# MCU.net
KiCad netlist of a schematic drawn in Altium Designer
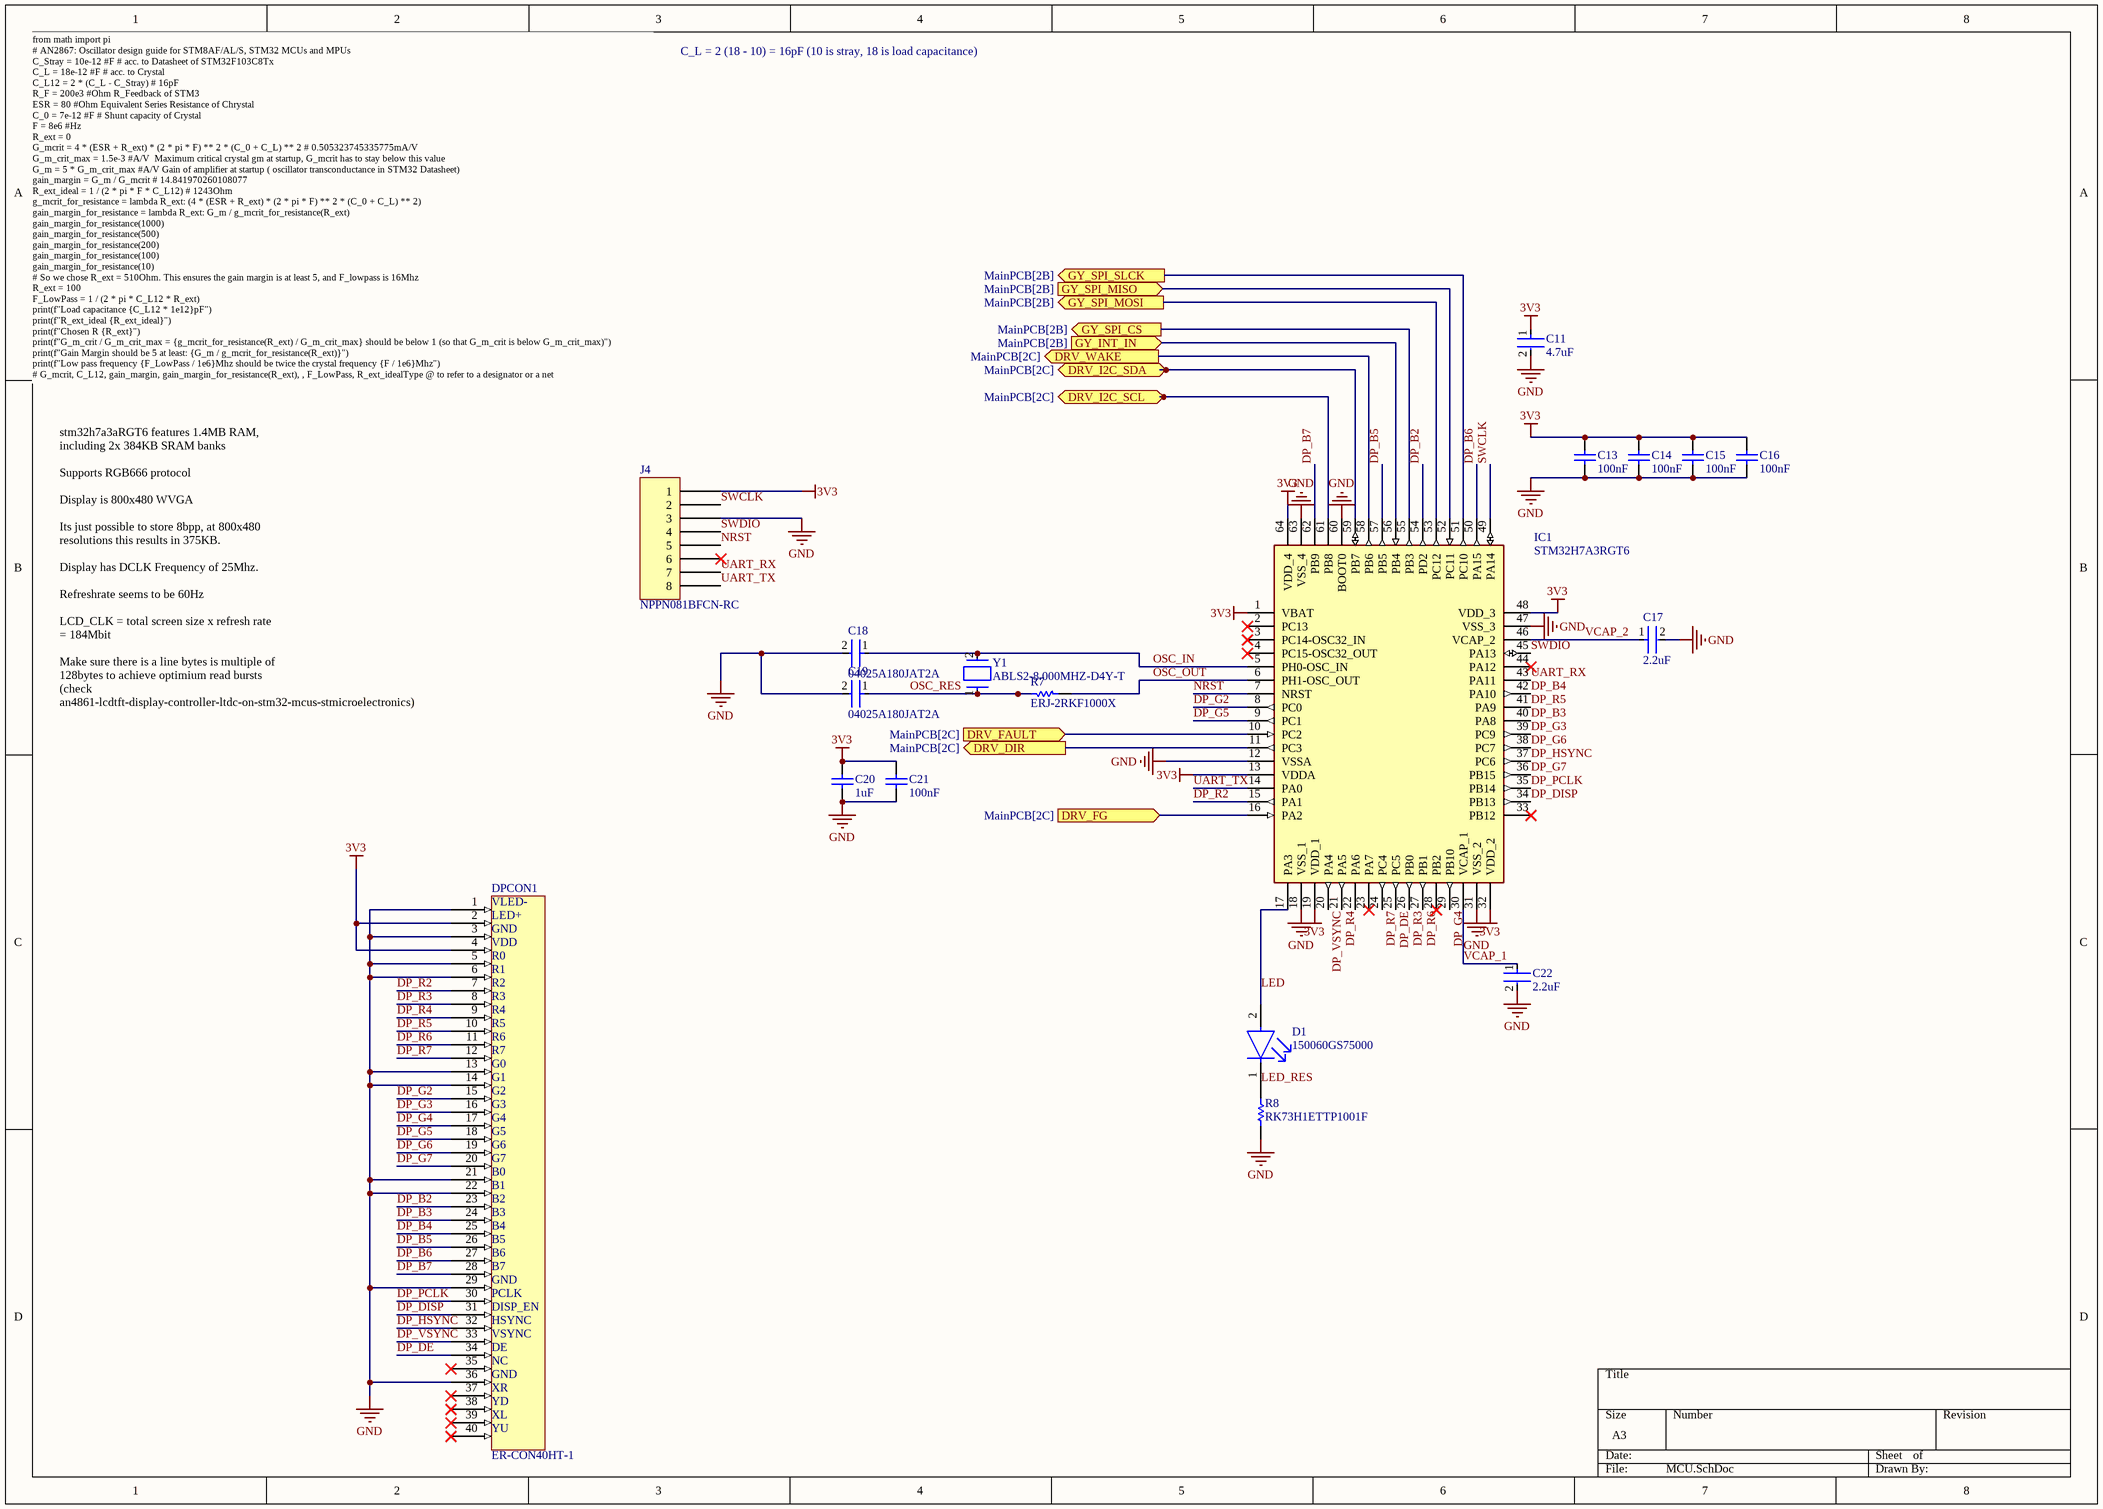
[diagram p0: MCU.SchDoc]

(export (version "E")
  (design (tool "Eeschema 10.0.6"))
  (components
    (comp (ref "C11")
      (value "4.7uF")
      (footprint "FP-C1005-050-0_15-MFG")
      (description "CAP CER 4.7UF 10V X5R 0402 C1005X5R1A475K050BC")
      (fields (field (name "TOLERANCE") "10%"))
      (libsource (lib "Altium Content Vault") (part "b4654b650e69147ec39a6b967a45e02"))
    )
    (comp (ref "C13")
      (value "100nF")
      (footprint "CAPC1005X56X25LL10T15")
      (description "04026D104KAT2A")
      (fields (field (name "MANUFACTURER") "AVX Interconnect / Elco"))
      (libsource (lib "Altium Content Vault") (part "CAP"))
    )
    (comp (ref "C14")
      (value "100nF")
      (footprint "CAPC1005X56X25LL10T15")
      (description "04026D104KAT2A")
      (fields (field (name "MANUFACTURER") "AVX Interconnect / Elco"))
      (libsource (lib "Altium Content Vault") (part "CAP"))
    )
    (comp (ref "C15")
      (value "100nF")
      (footprint "CAPC1005X56X25LL10T15")
      (description "04026D104KAT2A")
      (fields (field (name "MANUFACTURER") "AVX Interconnect / Elco"))
      (libsource (lib "Altium Content Vault") (part "CAP"))
    )
    (comp (ref "C16")
      (value "100nF")
      (footprint "CAPC1005X56X25LL10T15")
      (description "04026D104KAT2A")
      (fields (field (name "MANUFACTURER") "AVX Interconnect / Elco"))
      (libsource (lib "Altium Content Vault") (part "CAP"))
    )
    (comp (ref "C17")
      (value "2.2uF")
      (footprint "FP-C1005-050-0_05-IPC_A")
      (description "Multilayer Ceramic Capacitors 2.2μF ±10% 10V X5R SMD 0402 C1005X5R1A225K050BC")
      (fields (field (name "TOLERANCE") "10%") (field (name "VOLTAGE") "10V"))
      (libsource (lib "Altium Content Vault") (part "b4654b650e69147ec39a6b967a45e02"))
    )
    (comp (ref "C18")
      (value "04025A180JAT2A")
      (footprint "FP-0402-L_1_0_1-W_0_5_0_1-MFG")
      (description "General Purpose Ceramic Capacitor, 0402, 18pF, 5%, C0G, 30ppm/°C, 50V")
      (fields (field (name "VOLTAGE") "50V") (field (name "TOLERANCE") "5%"))
      (libsource (lib "Altium Content Vault") (part "b4654b650e69147ec39a6b967a45e02"))
    )
    (comp (ref "C19")
      (value "04025A180JAT2A")
      (footprint "FP-0402-L_1_0_1-W_0_5_0_1-MFG")
      (description "General Purpose Ceramic Capacitor, 0402, 18pF, 5%, C0G, 30ppm/°C, 50V")
      (fields (field (name "VOLTAGE") "50V") (field (name "TOLERANCE") "5%"))
      (libsource (lib "Altium Content Vault") (part "b4654b650e69147ec39a6b967a45e02"))
    )
    (comp (ref "C20")
      (value "1uF")
      (footprint "CAPC1005X60X30NL05T10")
      (description "C0402C105M8PACTU")
      (fields (field (name "MANUFACTURER") "Kemet"))
      (libsource (lib "Altium Content Vault") (part "CAP"))
    )
    (comp (ref "C21")
      (value "100nF")
      (footprint "CAPC1005X56X25LL10T15")
      (description "04026D104KAT2A")
      (fields (field (name "MANUFACTURER") "AVX Interconnect / Elco"))
      (libsource (lib "Altium Content Vault") (part "CAP"))
    )
    (comp (ref "C22")
      (value "2.2uF")
      (footprint "FP-C1005-050-0_05-IPC_A")
      (description "Multilayer Ceramic Capacitors 2.2μF ±10% 10V X5R SMD 0402 C1005X5R1A225K050BC")
      (fields (field (name "TOLERANCE") "10%") (field (name "VOLTAGE") "10V"))
      (libsource (lib "Altium Content Vault") (part "b4654b650e69147ec39a6b967a45e02"))
    )
    (comp (ref "D1")
      (value "150060GS75000")
      (footprint "FP-150060GS75000-MFG")
      (description "LED GREEN CLEAR 0603 SMD")
      (libsource (lib "Altium Content Vault") (part "8706943c75ba83719d021d2fdc84c58"))
    )
    (comp (ref "DPCON1")
      (value "ER-CON40HT-1")
      (footprint "ER-CON40HT-1")
      (fields (field (name "MANUFACTURER") "EastRising"))
      (libsource (lib "Schlib1") (part "ER-CON40HT-1"))
    )
    (comp (ref "IC1")
      (value "STM32H7A3RGT6")
      (footprint "SamacSys:QFP50P1200X1200X160-64N")
      (description "Integrated Circuit")
      (fields (field (name "MOUSER PART NUMBER") "511-STM32H7A3RGT6"))
      (libsource (lib "*") (part "STM32H7A3RGT6"))
    )
    (comp (ref "J4")
      (value "NPPN081BFCN-RC")
      (footprint "SULLINS NPPN081BFCN")
      (description "CONN HDR 8POS 0.079 GOLD PCB")
      (fields (field (name "MANUFACTURER") "Sullins Connector Solutions"))
      (libsource (lib "Celestial Altium Library") (part "8 Pin"))
    )
    (comp (ref "R7")
      (value "ERJ-2RKF1000X")
      (footprint "RESC1005X40X25LL05T05")
      (description "Chip Resistor, 100 Ohm, +/- 1%, 100 mW, -55 to 155 degC, 0402 (1005 Metric), RoHS, Tape and Reel")
      (fields (field (name "MANUFACTURER") "Basic Passives") (field (name "TOLERANCE") "1%"))
      (libsource (lib "Altium Content Vault") (part "RES-2"))
    )
    (comp (ref "R8")
      (value "RK73H1ETTP1001F")
      (footprint "RESC1005X40X25LL10T10")
      (fields (field (name "MANUFACTURER") "KOA Speer"))
      (libsource (lib "Altium Content Vault") (part "RES"))
    )
    (comp (ref "Y1")
      (value "ABLS2-8.000MHZ-D4Y-T")
      (footprint "FP-ABLS2-MFG")
      (description "CRYSTAL 8.0000MHZ 18PF SMD")
      (fields (field (name "TOLERANCE") "30ppm"))
      (libsource (lib "Altium Content Vault") (part "c23a69dc6c9e2f18f2079038eb95dd1"))
    )
  )
  (nets
    (net (code "1") (name "/DP_B2") (class "Default")
      (node (ref "DPCON1") (pin "23") (pintype "input"))
      (node (ref "IC1") (pin "54") (pinfunction "PD2_54") (pintype "output"))
    )
    (net (code "2") (name "/DP_B3") (class "Default")
      (node (ref "DPCON1") (pin "24") (pintype "input"))
      (node (ref "IC1") (pin "40") (pinfunction "PA8_40") (pintype "open_collector"))
    )
    (net (code "3") (name "/DP_B4") (class "Default")
      (node (ref "DPCON1") (pin "25") (pintype "input"))
      (node (ref "IC1") (pin "42") (pinfunction "PA10_42") (pintype "output"))
    )
    (net (code "4") (name "/DP_B5") (class "Default")
      (node (ref "DPCON1") (pin "26") (pintype "input"))
      (node (ref "IC1") (pin "57") (pinfunction "PB5_57") (pintype "output"))
    )
    (net (code "5") (name "/DP_B6") (class "Default")
      (node (ref "DPCON1") (pin "27") (pintype "input"))
      (node (ref "IC1") (pin "50") (pinfunction "PA15_50") (pintype "output"))
    )
    (net (code "6") (name "/DP_B7") (class "Default")
      (node (ref "DPCON1") (pin "28") (pintype "input"))
      (node (ref "IC1") (pin "62") (pinfunction "PB9_62") (pintype "open_collector"))
    )
    (net (code "7") (name "/DP_DE") (class "Default")
      (node (ref "DPCON1") (pin "34") (pintype "input"))
      (node (ref "IC1") (pin "25") (pinfunction "PC5_25") (pintype "output"))
    )
    (net (code "8") (name "/DP_DISP") (class "Default")
      (node (ref "DPCON1") (pin "31") (pintype "input"))
      (node (ref "IC1") (pin "34") (pinfunction "PB13_34") (pintype "output"))
    )
    (net (code "9") (name "/DP_G2") (class "Default")
      (node (ref "DPCON1") (pin "15") (pintype "input"))
      (node (ref "IC1") (pin "8") (pinfunction "PC0_8") (pintype "output"))
    )
    (net (code "10") (name "/DP_G3") (class "Default")
      (node (ref "DPCON1") (pin "16") (pintype "input"))
      (node (ref "IC1") (pin "39") (pinfunction "PC9_39") (pintype "output"))
    )
    (net (code "11") (name "/DP_G4") (class "Default")
      (node (ref "DPCON1") (pin "17") (pintype "input"))
      (node (ref "IC1") (pin "29") (pinfunction "PB10_29") (pintype "output"))
    )
    (net (code "12") (name "/DP_G5") (class "Default")
      (node (ref "DPCON1") (pin "18") (pintype "input"))
      (node (ref "IC1") (pin "9") (pinfunction "PC1_9") (pintype "output"))
    )
    (net (code "13") (name "/DP_G6") (class "Default")
      (node (ref "DPCON1") (pin "19") (pintype "input"))
      (node (ref "IC1") (pin "38") (pinfunction "PC7_38") (pintype "output"))
    )
    (net (code "14") (name "/DP_G7") (class "Default")
      (node (ref "DPCON1") (pin "20") (pintype "input"))
      (node (ref "IC1") (pin "36") (pinfunction "PB15_36") (pintype "output"))
    )
    (net (code "15") (name "/DP_HSYNC") (class "Default")
      (node (ref "DPCON1") (pin "32") (pintype "input"))
      (node (ref "IC1") (pin "37") (pinfunction "PC6_37") (pintype "output"))
    )
    (net (code "16") (name "/DP_PCLK") (class "Default")
      (node (ref "DPCON1") (pin "30") (pintype "input"))
      (node (ref "IC1") (pin "35") (pinfunction "PB14_35") (pintype "output"))
    )
    (net (code "17") (name "/DP_R2") (class "Default")
      (node (ref "DPCON1") (pin "7") (pintype "input"))
      (node (ref "IC1") (pin "15") (pinfunction "PA1_15") (pintype "output"))
    )
    (net (code "18") (name "/DP_R3") (class "Default")
      (node (ref "DPCON1") (pin "8") (pintype "input"))
      (node (ref "IC1") (pin "26") (pinfunction "PB0_26") (pintype "output"))
    )
    (net (code "19") (name "/DP_R4") (class "Default")
      (node (ref "DPCON1") (pin "9") (pintype "input"))
      (node (ref "IC1") (pin "21") (pinfunction "PA5_21") (pintype "output"))
    )
    (net (code "20") (name "/DP_R5") (class "Default")
      (node (ref "DPCON1") (pin "10") (pintype "input"))
      (node (ref "IC1") (pin "41") (pinfunction "PA9_41") (pintype "open_collector"))
    )
    (net (code "21") (name "/DP_R6") (class "Default")
      (node (ref "DPCON1") (pin "11") (pintype "input"))
      (node (ref "IC1") (pin "27") (pinfunction "PB1_27") (pintype "output"))
    )
    (net (code "22") (name "/DP_R7") (class "Default")
      (node (ref "DPCON1") (pin "12") (pintype "input"))
      (node (ref "IC1") (pin "24") (pinfunction "PC4_24") (pintype "output"))
    )
    (net (code "23") (name "/DP_VSYNC") (class "Default")
      (node (ref "DPCON1") (pin "33") (pintype "input"))
      (node (ref "IC1") (pin "20") (pinfunction "PA4_20") (pintype "output"))
    )
    (net (code "24") (name "/DRV_DIR") (class "Default")
      (node (ref "IC1") (pin "11") (pinfunction "PC3_11") (pintype "output"))
    )
    (net (code "25") (name "/DRV_FAULT") (class "Default")
      (node (ref "IC1") (pin "10") (pinfunction "PC2_10") (pintype "input"))
    )
    (net (code "26") (name "/DRV_FG") (class "Default")
      (node (ref "IC1") (pin "16") (pinfunction "PA2_16") (pintype "input"))
    )
    (net (code "27") (name "/DRV_I2C_SCL") (class "Default")
      (node (ref "IC1") (pin "61") (pinfunction "PB8_61") (pintype "open_collector"))
    )
    (net (code "28") (name "/DRV_I2C_SDA") (class "Default")
      (node (ref "IC1") (pin "59") (pinfunction "PB7_59") (pintype "bidirectional"))
    )
    (net (code "29") (name "/DRV_WAKE") (class "Default")
      (node (ref "IC1") (pin "58") (pinfunction "PB6_58") (pintype "output"))
    )
    (net (code "30") (name "/GY_INT_IN") (class "Default")
      (node (ref "IC1") (pin "56") (pinfunction "PB4_56") (pintype "input"))
    )
    (net (code "31") (name "/GY_SPI_CS") (class "Default")
      (node (ref "IC1") (pin "55") (pinfunction "PB3_55") (pintype "output"))
    )
    (net (code "32") (name "/GY_SPI_MISO") (class "Default")
      (node (ref "IC1") (pin "52") (pinfunction "PC11_52") (pintype "input"))
    )
    (net (code "33") (name "/GY_SPI_MOSI") (class "Default")
      (node (ref "IC1") (pin "53") (pinfunction "PC12_53") (pintype "output"))
    )
    (net (code "34") (name "/GY_SPI_SLCK") (class "Default")
      (node (ref "IC1") (pin "51") (pinfunction "PC10_51") (pintype "output"))
    )
    (net (code "35") (name "/LED") (class "Default")
      (node (ref "D1") (pin "2") (pinfunction "A_2") (pintype "passive"))
      (node (ref "IC1") (pin "17") (pinfunction "PA3_17") (pintype "passive"))
    )
    (net (code "36") (name "/LED_RES") (class "Default")
      (node (ref "D1") (pin "1") (pinfunction "C_1") (pintype "passive"))
      (node (ref "R8") (pin "2") (pinfunction "2_2") (pintype "passive"))
    )
    (net (code "37") (name "/NRST") (class "Default")
      (node (ref "IC1") (pin "7") (pinfunction "NRST_7") (pintype "passive"))
      (node (ref "J4") (pin "5") (pinfunction "5_5") (pintype "passive"))
    )
    (net (code "38") (name "/OSC_IN") (class "Default")
      (node (ref "C18") (pin "1") (pinfunction "1_1") (pintype "passive"))
      (node (ref "IC1") (pin "5") (pinfunction "PH0-OSC_IN_5") (pintype "passive"))
      (node (ref "Y1") (pin "2") (pinfunction "2_2") (pintype "passive"))
    )
    (net (code "39") (name "/OSC_OUT") (class "Default")
      (node (ref "IC1") (pin "6") (pinfunction "PH1-OSC_OUT_6") (pintype "passive"))
      (node (ref "R7") (pin "1") (pinfunction "1_1") (pintype "passive"))
    )
    (net (code "40") (name "/OSC_RES") (class "Default")
      (node (ref "C19") (pin "1") (pinfunction "1_1") (pintype "passive"))
      (node (ref "R7") (pin "2") (pinfunction "2_2") (pintype "passive"))
      (node (ref "Y1") (pin "1") (pinfunction "1_1") (pintype "passive"))
    )
    (net (code "41") (name "/SWCLK") (class "Default")
      (node (ref "IC1") (pin "49") (pinfunction "PA14_49") (pintype "bidirectional"))
      (node (ref "J4") (pin "2") (pinfunction "2_2") (pintype "passive"))
    )
    (net (code "42") (name "/SWDIO") (class "Default")
      (node (ref "IC1") (pin "45") (pinfunction "PA13_45") (pintype "bidirectional"))
      (node (ref "J4") (pin "4") (pinfunction "4_4") (pintype "passive"))
    )
    (net (code "43") (name "/UART_RX") (class "Default")
      (node (ref "IC1") (pin "43") (pinfunction "PA11_43") (pintype "passive"))
      (node (ref "J4") (pin "7") (pinfunction "7_7") (pintype "passive"))
    )
    (net (code "44") (name "/UART_TX") (class "Default")
      (node (ref "IC1") (pin "14") (pinfunction "PA0_14") (pintype "passive"))
      (node (ref "J4") (pin "8") (pinfunction "8_8") (pintype "passive"))
    )
    (net (code "45") (name "/VCAP_1") (class "Default")
      (node (ref "C22") (pin "1") (pinfunction "1_1") (pintype "passive"))
      (node (ref "IC1") (pin "30") (pinfunction "VCAP_1_30") (pintype "passive"))
    )
    (net (code "46") (name "/VCAP_2") (class "Default")
      (node (ref "C17") (pin "1") (pinfunction "1_1") (pintype "passive"))
      (node (ref "IC1") (pin "46") (pinfunction "VCAP_2_46") (pintype "passive"))
    )
    (net (code "47") (name "3V3") (class "Default")
      (node (ref "C11") (pin "1") (pinfunction "1_1") (pintype "passive"))
      (node (ref "C13") (pin "2") (pinfunction "2_2") (pintype "passive"))
      (node (ref "C14") (pin "2") (pinfunction "2_2") (pintype "passive"))
      (node (ref "C15") (pin "2") (pinfunction "2_2") (pintype "passive"))
      (node (ref "C16") (pin "2") (pinfunction "2_2") (pintype "passive"))
      (node (ref "C20") (pin "2") (pinfunction "2_2") (pintype "passive"))
      (node (ref "C21") (pin "2") (pinfunction "2_2") (pintype "passive"))
      (node (ref "DPCON1") (pin "2") (pintype "input"))
      (node (ref "DPCON1") (pin "4") (pintype "input"))
      (node (ref "IC1") (pin "1") (pinfunction "VBAT_1") (pintype "power_in"))
      (node (ref "IC1") (pin "13") (pinfunction "VDDA_13") (pintype "power_in"))
      (node (ref "IC1") (pin "19") (pinfunction "VDD_1_19") (pintype "power_in"))
      (node (ref "IC1") (pin "32") (pinfunction "VDD_2_32") (pintype "power_in"))
      (node (ref "IC1") (pin "48") (pinfunction "VDD_3_48") (pintype "power_in"))
      (node (ref "IC1") (pin "64") (pinfunction "VDD_4_64") (pintype "power_in"))
      (node (ref "J4") (pin "1") (pinfunction "1_1") (pintype "passive"))
    )
    (net (code "48") (name "GND") (class "Default")
      (node (ref "C11") (pin "2") (pinfunction "2_2") (pintype "passive"))
      (node (ref "C13") (pin "1") (pinfunction "1_1") (pintype "passive"))
      (node (ref "C14") (pin "1") (pinfunction "1_1") (pintype "passive"))
      (node (ref "C15") (pin "1") (pinfunction "1_1") (pintype "passive"))
      (node (ref "C16") (pin "1") (pinfunction "1_1") (pintype "passive"))
      (node (ref "C17") (pin "2") (pinfunction "2_2") (pintype "passive"))
      (node (ref "C18") (pin "2") (pinfunction "2_2") (pintype "passive"))
      (node (ref "C19") (pin "2") (pinfunction "2_2") (pintype "passive"))
      (node (ref "C20") (pin "1") (pinfunction "1_1") (pintype "passive"))
      (node (ref "C21") (pin "1") (pinfunction "1_1") (pintype "passive"))
      (node (ref "C22") (pin "2") (pinfunction "2_2") (pintype "passive"))
      (node (ref "DPCON1") (pin "1") (pintype "input"))
      (node (ref "DPCON1") (pin "13") (pintype "input"))
      (node (ref "DPCON1") (pin "14") (pintype "input"))
      (node (ref "DPCON1") (pin "21") (pintype "input"))
      (node (ref "DPCON1") (pin "22") (pintype "input"))
      (node (ref "DPCON1") (pin "29") (pintype "input"))
      (node (ref "DPCON1") (pin "3") (pintype "input"))
      (node (ref "DPCON1") (pin "36") (pintype "input"))
      (node (ref "DPCON1") (pin "5") (pintype "input"))
      (node (ref "DPCON1") (pin "6") (pintype "input"))
      (node (ref "IC1") (pin "12") (pinfunction "VSSA_12") (pintype "power_in"))
      (node (ref "IC1") (pin "18") (pinfunction "VSS_1_18") (pintype "power_in"))
      (node (ref "IC1") (pin "31") (pinfunction "VSS_2_31") (pintype "power_in"))
      (node (ref "IC1") (pin "47") (pinfunction "VSS_3_47") (pintype "power_in"))
      (node (ref "IC1") (pin "60") (pinfunction "BOOT0_60") (pintype "passive"))
      (node (ref "IC1") (pin "63") (pinfunction "VSS_4_63") (pintype "power_in"))
      (node (ref "J4") (pin "3") (pinfunction "3_3") (pintype "passive"))
      (node (ref "R8") (pin "1") (pinfunction "1_1") (pintype "passive"))
    )
    (net (code "49") (name "unconnected-(DPCON1-Pad35)") (class "Default")
      (node (ref "DPCON1") (pin "35") (pintype "input+no_connect"))
    )
    (net (code "50") (name "unconnected-(DPCON1-Pad37)") (class "Default")
      (node (ref "DPCON1") (pin "37") (pintype "input+no_connect"))
    )
    (net (code "51") (name "unconnected-(DPCON1-Pad38)") (class "Default")
      (node (ref "DPCON1") (pin "38") (pintype "input+no_connect"))
    )
    (net (code "52") (name "unconnected-(DPCON1-Pad39)") (class "Default")
      (node (ref "DPCON1") (pin "39") (pintype "input+no_connect"))
    )
    (net (code "53") (name "unconnected-(DPCON1-Pad40)") (class "Default")
      (node (ref "DPCON1") (pin "40") (pintype "input+no_connect"))
    )
    (net (code "54") (name "unconnected-(IC1-PA6-Pad22)") (class "Default")
      (node (ref "IC1") (pin "22") (pinfunction "PA6_22") (pintype "passive"))
    )
    (net (code "55") (name "unconnected-(IC1-PA7-Pad23)") (class "Default")
      (node (ref "IC1") (pin "23") (pinfunction "PA7_23") (pintype "passive+no_connect"))
    )
    (net (code "56") (name "unconnected-(IC1-PA12-Pad44)") (class "Default")
      (node (ref "IC1") (pin "44") (pinfunction "PA12_44") (pintype "passive+no_connect"))
    )
    (net (code "57") (name "unconnected-(IC1-PB2-Pad28)") (class "Default")
      (node (ref "IC1") (pin "28") (pinfunction "PB2_28") (pintype "passive+no_connect"))
    )
    (net (code "58") (name "unconnected-(IC1-PB12-Pad33)") (class "Default")
      (node (ref "IC1") (pin "33") (pinfunction "PB12_33") (pintype "passive+no_connect"))
    )
    (net (code "59") (name "unconnected-(IC1-PC13-Pad2)") (class "Default")
      (node (ref "IC1") (pin "2") (pinfunction "PC13_2") (pintype "passive+no_connect"))
    )
    (net (code "60") (name "unconnected-(IC1-PC14-OSC32_IN-Pad3)") (class "Default")
      (node (ref "IC1") (pin "3") (pinfunction "PC14-OSC32_IN_3") (pintype "passive+no_connect"))
    )
    (net (code "61") (name "unconnected-(IC1-PC15-OSC32_OUT-Pad4)") (class "Default")
      (node (ref "IC1") (pin "4") (pinfunction "PC15-OSC32_OUT_4") (pintype "passive+no_connect"))
    )
    (net (code "62") (name "unconnected-(J4-Pad6)") (class "Default")
      (node (ref "J4") (pin "6") (pinfunction "6_6") (pintype "passive+no_connect"))
    )
  )
)
